# Sheet1.net
KiCad netlist of a schematic drawn in Altium Designer
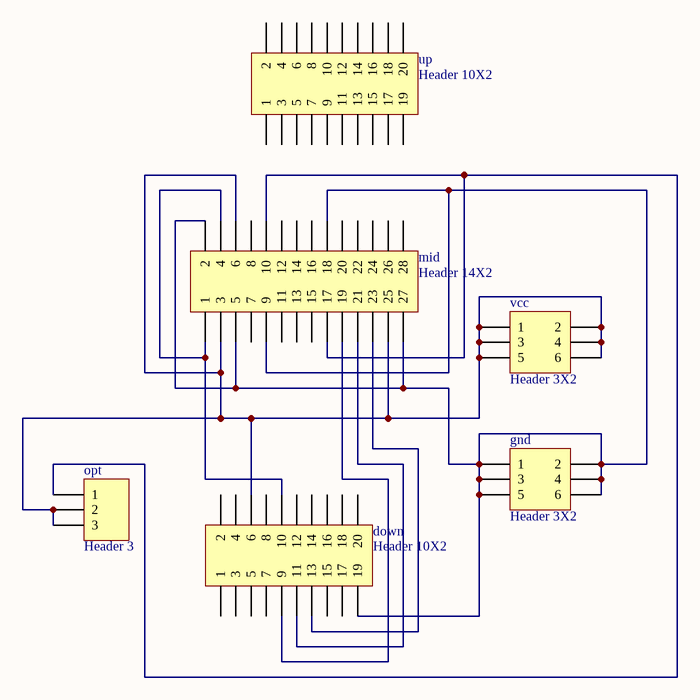
[diagram p0: Sheet1.SchDoc]

(export (version "E")
  (design (tool "Eeschema 10.0.6"))
  (components
    (comp (ref "down")
      (value "Header 10X2")
      (footprint "HDR2X10")
      (description "Header, 10-Pin, Dual row")
      (fields (field (name "PUBLISHER") "Altium Limited"))
      (libsource (lib "Miscellaneous Connectors") (part "Header 10X2"))
    )
    (comp (ref "gnd")
      (value "Header 3X2")
      (footprint "HDR2X3")
      (description "Header, 3-Pin, Dual row")
      (fields (field (name "PUBLISHER") "Altium Limited"))
      (libsource (lib "Miscellaneous Connectors") (part "Header 3X2"))
    )
    (comp (ref "mid")
      (value "Header 14X2")
      (footprint "HDR2X14")
      (description "Header, 14-Pin, Dual row")
      (fields (field (name "PUBLISHER") "Altium Limited"))
      (libsource (lib "Miscellaneous Connectors") (part "Header 14X2"))
    )
    (comp (ref "opt")
      (value "Header 3")
      (footprint "HDR1X3")
      (description "Header, 3-Pin")
      (fields (field (name "PUBLISHER") "Altium Limited"))
      (libsource (lib "Miscellaneous Connectors") (part "Header 3"))
    )
    (comp (ref "up")
      (value "Header 10X2")
      (footprint "HDR2X10")
      (description "Header, 10-Pin, Dual row")
      (fields (field (name "PUBLISHER") "Altium Limited"))
      (libsource (lib "Miscellaneous Connectors") (part "Header 10X2"))
    )
    (comp (ref "vcc")
      (value "Header 3X2")
      (footprint "HDR2X3")
      (description "Header, 3-Pin, Dual row")
      (fields (field (name "PUBLISHER") "Altium Limited"))
      (libsource (lib "Miscellaneous Connectors") (part "Header 3X2"))
    )
  )
  (nets
    (net (code "1") (name "Net-(down-Pad6)") (class "Default")
      (node (ref "down") (pin "6") (pinfunction "6_6") (pintype "passive"))
      (node (ref "mid") (pin "25") (pinfunction "25_25") (pintype "passive"))
      (node (ref "mid") (pin "3") (pinfunction "3_3") (pintype "passive"))
      (node (ref "mid") (pin "6") (pinfunction "6_6") (pintype "passive"))
      (node (ref "opt") (pin "2") (pinfunction "2_2") (pintype "passive"))
      (node (ref "opt") (pin "3") (pinfunction "3_3") (pintype "passive"))
      (node (ref "vcc") (pin "1") (pinfunction "1_1") (pintype "passive"))
      (node (ref "vcc") (pin "2") (pinfunction "2_2") (pintype "passive"))
      (node (ref "vcc") (pin "3") (pinfunction "3_3") (pintype "passive"))
      (node (ref "vcc") (pin "4") (pinfunction "4_4") (pintype "passive"))
      (node (ref "vcc") (pin "5") (pinfunction "5_5") (pintype "passive"))
      (node (ref "vcc") (pin "6") (pinfunction "6_6") (pintype "passive"))
    )
    (net (code "2") (name "Net-(down-Pad9)") (class "Default")
      (node (ref "down") (pin "9") (pinfunction "9_9") (pintype "passive"))
      (node (ref "mid") (pin "19") (pinfunction "19_19") (pintype "passive"))
    )
    (net (code "3") (name "Net-(down-Pad10)") (class "Default")
      (node (ref "down") (pin "10") (pinfunction "10_10") (pintype "passive"))
      (node (ref "mid") (pin "1") (pinfunction "1_1") (pintype "passive"))
      (node (ref "mid") (pin "4") (pinfunction "4_4") (pintype "passive"))
    )
    (net (code "4") (name "Net-(down-Pad11)") (class "Default")
      (node (ref "down") (pin "11") (pinfunction "11_11") (pintype "passive"))
      (node (ref "mid") (pin "21") (pinfunction "21_21") (pintype "passive"))
    )
    (net (code "5") (name "Net-(down-Pad13)") (class "Default")
      (node (ref "down") (pin "13") (pinfunction "13_13") (pintype "passive"))
      (node (ref "mid") (pin "23") (pinfunction "23_23") (pintype "passive"))
    )
    (net (code "6") (name "Net-(down-Pad19)") (class "Default")
      (node (ref "down") (pin "19") (pinfunction "19_19") (pintype "passive"))
      (node (ref "gnd") (pin "1") (pinfunction "1_1") (pintype "passive"))
      (node (ref "gnd") (pin "2") (pinfunction "2_2") (pintype "passive"))
      (node (ref "gnd") (pin "3") (pinfunction "3_3") (pintype "passive"))
      (node (ref "gnd") (pin "4") (pinfunction "4_4") (pintype "passive"))
      (node (ref "gnd") (pin "5") (pinfunction "5_5") (pintype "passive"))
      (node (ref "gnd") (pin "6") (pinfunction "6_6") (pintype "passive"))
      (node (ref "mid") (pin "18") (pinfunction "18_18") (pintype "passive"))
      (node (ref "mid") (pin "2") (pinfunction "2_2") (pintype "passive"))
      (node (ref "mid") (pin "27") (pinfunction "27_27") (pintype "passive"))
      (node (ref "mid") (pin "5") (pinfunction "5_5") (pintype "passive"))
      (node (ref "mid") (pin "9") (pinfunction "9_9") (pintype "passive"))
    )
    (net (code "7") (name "Net-(mid-Pad10)") (class "Default")
      (node (ref "mid") (pin "10") (pinfunction "10_10") (pintype "passive"))
      (node (ref "mid") (pin "17") (pinfunction "17_17") (pintype "passive"))
      (node (ref "opt") (pin "1") (pinfunction "1_1") (pintype "passive"))
    )
    (net (code "8") (name "unconnected-(down-Pad1)") (class "Default")
      (node (ref "down") (pin "1") (pinfunction "1_1") (pintype "passive"))
    )
    (net (code "9") (name "unconnected-(down-Pad2)") (class "Default")
      (node (ref "down") (pin "2") (pinfunction "2_2") (pintype "passive"))
    )
    (net (code "10") (name "unconnected-(down-Pad3)") (class "Default")
      (node (ref "down") (pin "3") (pinfunction "3_3") (pintype "passive"))
    )
    (net (code "11") (name "unconnected-(down-Pad4)") (class "Default")
      (node (ref "down") (pin "4") (pinfunction "4_4") (pintype "passive"))
    )
    (net (code "12") (name "unconnected-(down-Pad5)") (class "Default")
      (node (ref "down") (pin "5") (pinfunction "5_5") (pintype "passive"))
    )
    (net (code "13") (name "unconnected-(down-Pad7)") (class "Default")
      (node (ref "down") (pin "7") (pinfunction "7_7") (pintype "passive"))
    )
    (net (code "14") (name "unconnected-(down-Pad8)") (class "Default")
      (node (ref "down") (pin "8") (pinfunction "8_8") (pintype "passive"))
    )
    (net (code "15") (name "unconnected-(down-Pad12)") (class "Default")
      (node (ref "down") (pin "12") (pinfunction "12_12") (pintype "passive"))
    )
    (net (code "16") (name "unconnected-(down-Pad14)") (class "Default")
      (node (ref "down") (pin "14") (pinfunction "14_14") (pintype "passive"))
    )
    (net (code "17") (name "unconnected-(down-Pad15)") (class "Default")
      (node (ref "down") (pin "15") (pinfunction "15_15") (pintype "passive"))
    )
    (net (code "18") (name "unconnected-(down-Pad16)") (class "Default")
      (node (ref "down") (pin "16") (pinfunction "16_16") (pintype "passive"))
    )
    (net (code "19") (name "unconnected-(down-Pad17)") (class "Default")
      (node (ref "down") (pin "17") (pinfunction "17_17") (pintype "passive"))
    )
    (net (code "20") (name "unconnected-(down-Pad18)") (class "Default")
      (node (ref "down") (pin "18") (pinfunction "18_18") (pintype "passive"))
    )
    (net (code "21") (name "unconnected-(down-Pad20)") (class "Default")
      (node (ref "down") (pin "20") (pinfunction "20_20") (pintype "passive"))
    )
    (net (code "22") (name "unconnected-(mid-Pad7)") (class "Default")
      (node (ref "mid") (pin "7") (pinfunction "7_7") (pintype "passive"))
    )
    (net (code "23") (name "unconnected-(mid-Pad8)") (class "Default")
      (node (ref "mid") (pin "8") (pinfunction "8_8") (pintype "passive"))
    )
    (net (code "24") (name "unconnected-(mid-Pad11)") (class "Default")
      (node (ref "mid") (pin "11") (pinfunction "11_11") (pintype "passive"))
    )
    (net (code "25") (name "unconnected-(mid-Pad12)") (class "Default")
      (node (ref "mid") (pin "12") (pinfunction "12_12") (pintype "passive"))
    )
    (net (code "26") (name "unconnected-(mid-Pad13)") (class "Default")
      (node (ref "mid") (pin "13") (pinfunction "13_13") (pintype "passive"))
    )
    (net (code "27") (name "unconnected-(mid-Pad14)") (class "Default")
      (node (ref "mid") (pin "14") (pinfunction "14_14") (pintype "passive"))
    )
    (net (code "28") (name "unconnected-(mid-Pad15)") (class "Default")
      (node (ref "mid") (pin "15") (pinfunction "15_15") (pintype "passive"))
    )
    (net (code "29") (name "unconnected-(mid-Pad16)") (class "Default")
      (node (ref "mid") (pin "16") (pinfunction "16_16") (pintype "passive"))
    )
    (net (code "30") (name "unconnected-(mid-Pad20)") (class "Default")
      (node (ref "mid") (pin "20") (pinfunction "20_20") (pintype "passive"))
    )
    (net (code "31") (name "unconnected-(mid-Pad22)") (class "Default")
      (node (ref "mid") (pin "22") (pinfunction "22_22") (pintype "passive"))
    )
    (net (code "32") (name "unconnected-(mid-Pad24)") (class "Default")
      (node (ref "mid") (pin "24") (pinfunction "24_24") (pintype "passive"))
    )
    (net (code "33") (name "unconnected-(mid-Pad26)") (class "Default")
      (node (ref "mid") (pin "26") (pinfunction "26_26") (pintype "passive"))
    )
    (net (code "34") (name "unconnected-(mid-Pad28)") (class "Default")
      (node (ref "mid") (pin "28") (pinfunction "28_28") (pintype "passive"))
    )
    (net (code "35") (name "unconnected-(up-Pad1)") (class "Default")
      (node (ref "up") (pin "1") (pinfunction "1_1") (pintype "passive"))
    )
    (net (code "36") (name "unconnected-(up-Pad2)") (class "Default")
      (node (ref "up") (pin "2") (pinfunction "2_2") (pintype "passive"))
    )
    (net (code "37") (name "unconnected-(up-Pad3)") (class "Default")
      (node (ref "up") (pin "3") (pinfunction "3_3") (pintype "passive"))
    )
    (net (code "38") (name "unconnected-(up-Pad4)") (class "Default")
      (node (ref "up") (pin "4") (pinfunction "4_4") (pintype "passive"))
    )
    (net (code "39") (name "unconnected-(up-Pad5)") (class "Default")
      (node (ref "up") (pin "5") (pinfunction "5_5") (pintype "passive"))
    )
    (net (code "40") (name "unconnected-(up-Pad6)") (class "Default")
      (node (ref "up") (pin "6") (pinfunction "6_6") (pintype "passive"))
    )
    (net (code "41") (name "unconnected-(up-Pad7)") (class "Default")
      (node (ref "up") (pin "7") (pinfunction "7_7") (pintype "passive"))
    )
    (net (code "42") (name "unconnected-(up-Pad8)") (class "Default")
      (node (ref "up") (pin "8") (pinfunction "8_8") (pintype "passive"))
    )
    (net (code "43") (name "unconnected-(up-Pad9)") (class "Default")
      (node (ref "up") (pin "9") (pinfunction "9_9") (pintype "passive"))
    )
    (net (code "44") (name "unconnected-(up-Pad10)") (class "Default")
      (node (ref "up") (pin "10") (pinfunction "10_10") (pintype "passive"))
    )
    (net (code "45") (name "unconnected-(up-Pad11)") (class "Default")
      (node (ref "up") (pin "11") (pinfunction "11_11") (pintype "passive"))
    )
    (net (code "46") (name "unconnected-(up-Pad12)") (class "Default")
      (node (ref "up") (pin "12") (pinfunction "12_12") (pintype "passive"))
    )
    (net (code "47") (name "unconnected-(up-Pad13)") (class "Default")
      (node (ref "up") (pin "13") (pinfunction "13_13") (pintype "passive"))
    )
    (net (code "48") (name "unconnected-(up-Pad14)") (class "Default")
      (node (ref "up") (pin "14") (pinfunction "14_14") (pintype "passive"))
    )
    (net (code "49") (name "unconnected-(up-Pad15)") (class "Default")
      (node (ref "up") (pin "15") (pinfunction "15_15") (pintype "passive"))
    )
    (net (code "50") (name "unconnected-(up-Pad16)") (class "Default")
      (node (ref "up") (pin "16") (pinfunction "16_16") (pintype "passive"))
    )
    (net (code "51") (name "unconnected-(up-Pad17)") (class "Default")
      (node (ref "up") (pin "17") (pinfunction "17_17") (pintype "passive"))
    )
    (net (code "52") (name "unconnected-(up-Pad18)") (class "Default")
      (node (ref "up") (pin "18") (pinfunction "18_18") (pintype "passive"))
    )
    (net (code "53") (name "unconnected-(up-Pad19)") (class "Default")
      (node (ref "up") (pin "19") (pinfunction "19_19") (pintype "passive"))
    )
    (net (code "54") (name "unconnected-(up-Pad20)") (class "Default")
      (node (ref "up") (pin "20") (pinfunction "20_20") (pintype "passive"))
    )
  )
)
